# tick-wifi-mk-0_9.net
KiCad netlist of a schematic drawn in EAGLE
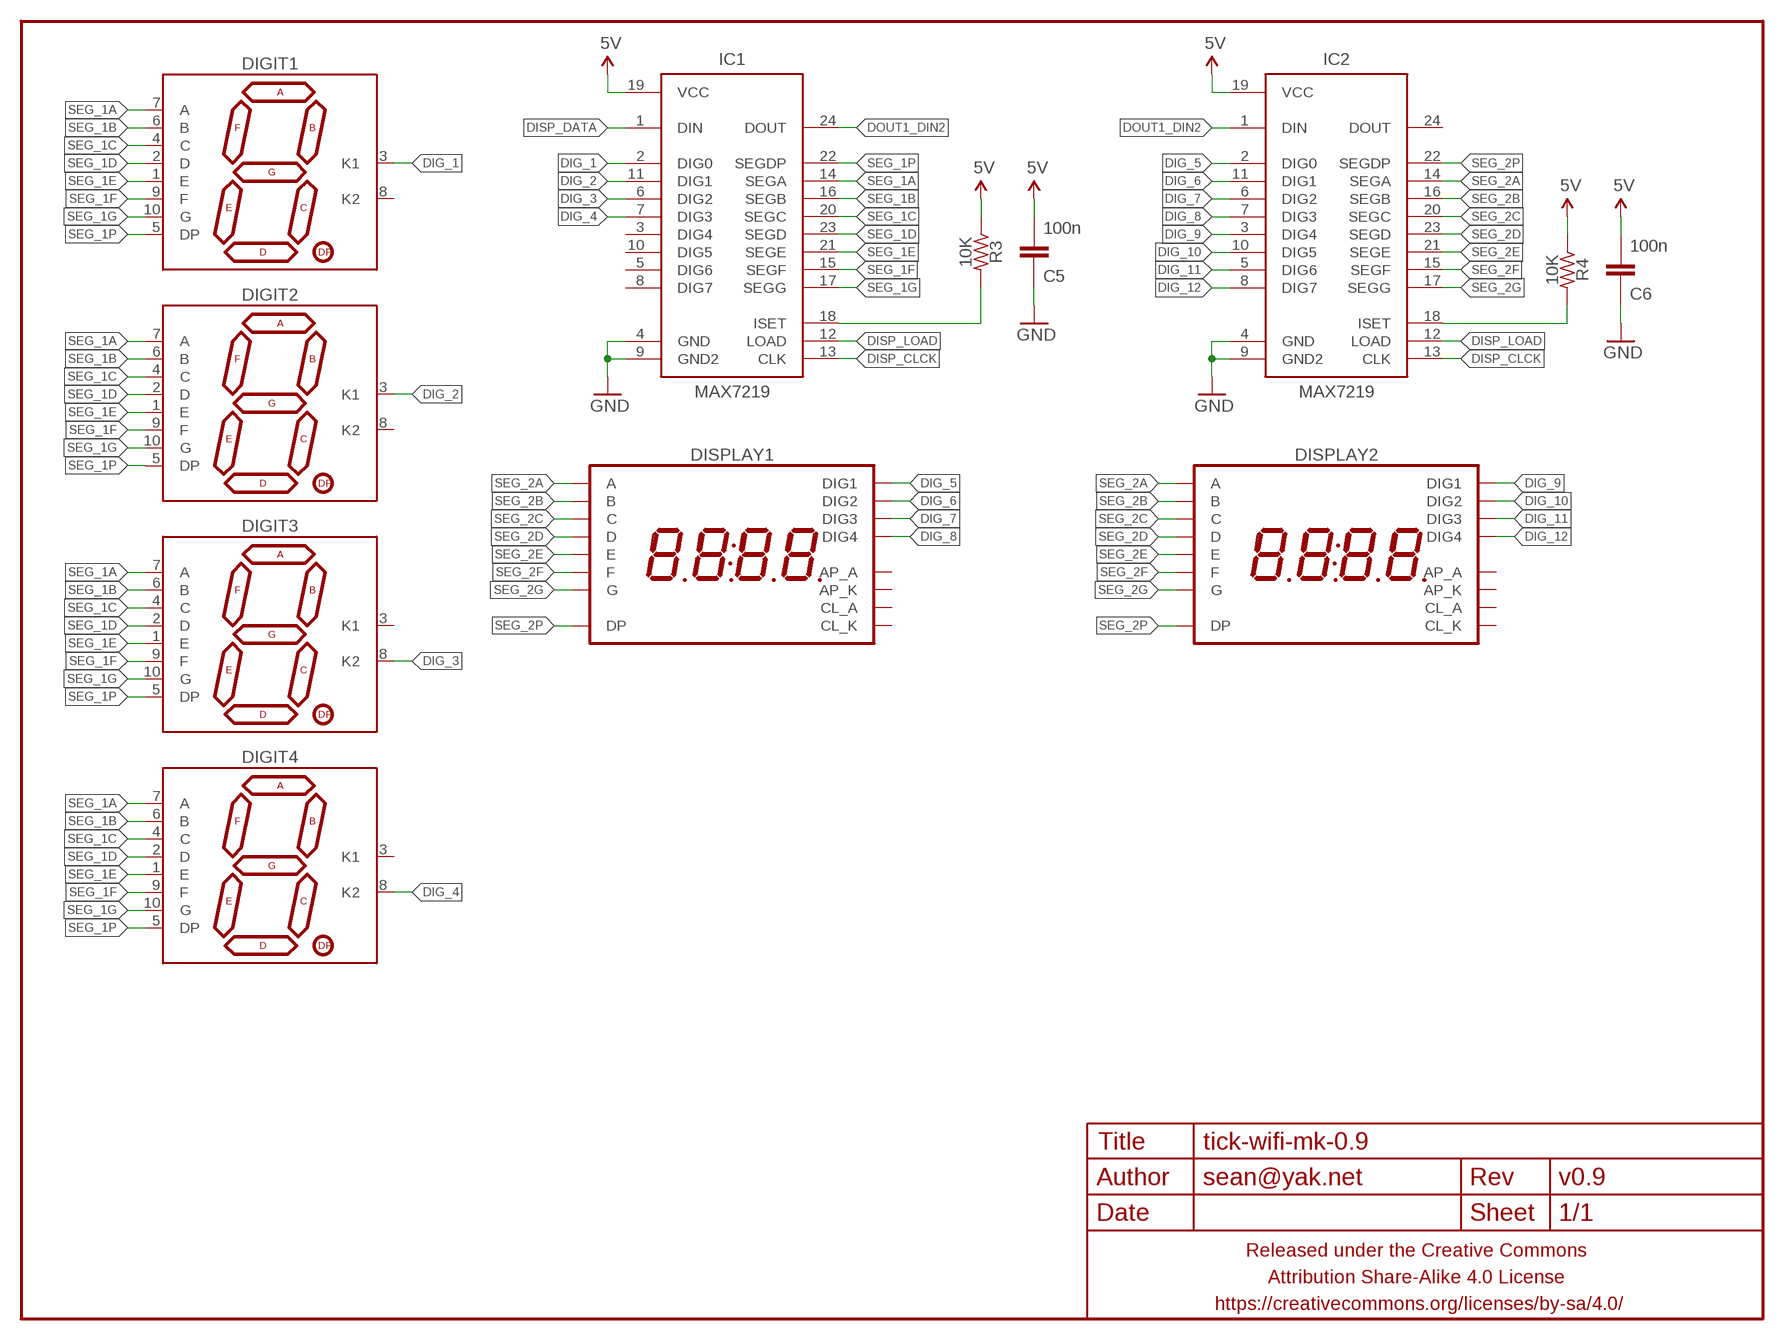
[diagram p0: schematic, sheet 1]

(export (version "E")
  (design (tool "Eeschema 10.0.6"))
  (components
    (comp (ref "C5")
      (value "100n")
      (footprint "eagle-import:C0603")
      (libsource (lib "eagle-import") (part "CAPACITOR-CERAMICC0603"))
    )
    (comp (ref "C6")
      (value "100n")
      (footprint "eagle-import:C0603")
      (libsource (lib "eagle-import") (part "CAPACITOR-CERAMICC0603"))
    )
    (comp (ref "DIGIT1")
      (value "7SEG_1DIGPTH-25.4MM-BARE")
      (footprint "eagle-import:7SEG_1DIG_25.4MM_NOSILK")
      (libsource (lib "eagle-import") (part "7SEG_1DIGPTH-25.4MM-BARE"))
    )
    (comp (ref "DIGIT2")
      (value "7SEG_1DIGPTH-25.4MM-BARE")
      (footprint "eagle-import:7SEG_1DIG_25.4MM_NOSILK")
      (libsource (lib "eagle-import") (part "7SEG_1DIGPTH-25.4MM-BARE"))
    )
    (comp (ref "DIGIT3")
      (value "7SEG_1DIGPTH-25.4MM-BARE")
      (footprint "eagle-import:7SEG_1DIG_25.4MM_NOSILK")
      (libsource (lib "eagle-import") (part "7SEG_1DIGPTH-25.4MM-BARE"))
    )
    (comp (ref "DIGIT4")
      (value "7SEG_1DIGPTH-25.4MM-BARE")
      (footprint "eagle-import:7SEG_1DIG_25.4MM_NOSILK")
      (libsource (lib "eagle-import") (part "7SEG_1DIGPTH-25.4MM-BARE"))
    )
    (comp (ref "DISPLAY1")
      (value "7SEG_4DIGIT_COLON_APOS")
      (footprint "eagle-import:7SEG_4DIG_10MM")
      (libsource (lib "eagle-import") (part "7SEG_4DIGIT_COLON_APOS"))
    )
    (comp (ref "DISPLAY2")
      (value "7SEG_4DIGIT_COLON_APOS")
      (footprint "eagle-import:7SEG_4DIG_10MM")
      (libsource (lib "eagle-import") (part "7SEG_4DIGIT_COLON_APOS"))
    )
    (comp (ref "FRAME1")
      (value "FRAME-LETTERNO_PACKAGE")
      (footprint "eagle-import:DUMMY")
      (fields (field (name "DESIGNER") "sean@yak.net") (field (name "VERSION") "v0.9"))
      (libsource (lib "eagle-import") (part "FRAME-LETTERNO_PACKAGE"))
    )
    (comp (ref "IC1")
      (value "MAX7219")
      (footprint "eagle-import:SO24W")
      (libsource (lib "eagle-import") (part "MAX7219SOIC-W"))
    )
    (comp (ref "IC2")
      (value "MAX7219")
      (footprint "eagle-import:SO24W")
      (libsource (lib "eagle-import") (part "MAX7219SOIC-W"))
    )
    (comp (ref "R3")
      (value "10K")
      (footprint "eagle-import:R0603")
      (libsource (lib "eagle-import") (part "RESISTORR0603"))
    )
    (comp (ref "R4")
      (value "10K")
      (footprint "eagle-import:R0603")
      (libsource (lib "eagle-import") (part "RESISTORR0603"))
    )
  )
  (nets
    (net (code "1") (name "5V") (class "Default")
      (node (ref "C5") (pin "2") (pinfunction "2_2") (pintype "passive"))
      (node (ref "C6") (pin "2") (pinfunction "2_2") (pintype "passive"))
      (node (ref "IC1") (pin "19") (pinfunction "VCC_19") (pintype "bidirectional"))
      (node (ref "IC2") (pin "19") (pinfunction "VCC_19") (pintype "bidirectional"))
      (node (ref "R3") (pin "1") (pinfunction "1_1") (pintype "passive"))
      (node (ref "R4") (pin "1") (pinfunction "1_1") (pintype "passive"))
    )
    (net (code "2") (name "DIG_1") (class "Default")
      (node (ref "DIGIT1") (pin "3") (pinfunction "K1_3") (pintype "bidirectional"))
      (node (ref "IC1") (pin "2") (pinfunction "DIG0_2") (pintype "bidirectional"))
    )
    (net (code "3") (name "DIG_2") (class "Default")
      (node (ref "DIGIT2") (pin "3") (pinfunction "K1_3") (pintype "bidirectional"))
      (node (ref "IC1") (pin "11") (pinfunction "DIG1_11") (pintype "bidirectional"))
    )
    (net (code "4") (name "DIG_3") (class "Default")
      (node (ref "DIGIT3") (pin "8") (pinfunction "K2_8") (pintype "bidirectional"))
      (node (ref "IC1") (pin "6") (pinfunction "DIG2_6") (pintype "bidirectional"))
    )
    (net (code "5") (name "DIG_4") (class "Default")
      (node (ref "DIGIT4") (pin "8") (pinfunction "K2_8") (pintype "bidirectional"))
      (node (ref "IC1") (pin "7") (pinfunction "DIG3_7") (pintype "bidirectional"))
    )
    (net (code "6") (name "DIG_5") (class "Default")
      (node (ref "DISPLAY1") (pin "1") (pinfunction "DIG1_1") (pintype "passive"))
      (node (ref "IC2") (pin "2") (pinfunction "DIG0_2") (pintype "bidirectional"))
    )
    (net (code "7") (name "DIG_6") (class "Default")
      (node (ref "DISPLAY1") (pin "2") (pinfunction "DIG2_2") (pintype "passive"))
      (node (ref "IC2") (pin "11") (pinfunction "DIG1_11") (pintype "bidirectional"))
    )
    (net (code "8") (name "DIG_7") (class "Default")
      (node (ref "DISPLAY1") (pin "6") (pinfunction "DIG3_6") (pintype "passive"))
      (node (ref "IC2") (pin "6") (pinfunction "DIG2_6") (pintype "bidirectional"))
    )
    (net (code "9") (name "DIG_8") (class "Default")
      (node (ref "DISPLAY1") (pin "8") (pinfunction "DIG4_8") (pintype "passive"))
      (node (ref "IC2") (pin "7") (pinfunction "DIG3_7") (pintype "bidirectional"))
    )
    (net (code "10") (name "DIG_9") (class "Default")
      (node (ref "DISPLAY2") (pin "1") (pinfunction "DIG1_1") (pintype "passive"))
      (node (ref "IC2") (pin "3") (pinfunction "DIG4_3") (pintype "bidirectional"))
    )
    (net (code "11") (name "DIG_10") (class "Default")
      (node (ref "DISPLAY2") (pin "2") (pinfunction "DIG2_2") (pintype "passive"))
      (node (ref "IC2") (pin "10") (pinfunction "DIG5_10") (pintype "bidirectional"))
    )
    (net (code "12") (name "DIG_11") (class "Default")
      (node (ref "DISPLAY2") (pin "6") (pinfunction "DIG3_6") (pintype "passive"))
      (node (ref "IC2") (pin "5") (pinfunction "DIG6_5") (pintype "bidirectional"))
    )
    (net (code "13") (name "DIG_12") (class "Default")
      (node (ref "DISPLAY2") (pin "8") (pinfunction "DIG4_8") (pintype "passive"))
      (node (ref "IC2") (pin "8") (pinfunction "DIG7_8") (pintype "bidirectional"))
    )
    (net (code "14") (name "DISP_CLCK") (class "Default")
      (node (ref "IC1") (pin "13") (pinfunction "CLK_13") (pintype "bidirectional"))
      (node (ref "IC2") (pin "13") (pinfunction "CLK_13") (pintype "bidirectional"))
    )
    (net (code "15") (name "DISP_DATA") (class "Default")
      (node (ref "IC1") (pin "1") (pinfunction "DIN_1") (pintype "bidirectional"))
    )
    (net (code "16") (name "DISP_LOAD") (class "Default")
      (node (ref "IC1") (pin "12") (pinfunction "LOAD_12") (pintype "bidirectional"))
      (node (ref "IC2") (pin "12") (pinfunction "LOAD_12") (pintype "bidirectional"))
    )
    (net (code "17") (name "DOUT1_DIN2") (class "Default")
      (node (ref "IC1") (pin "24") (pinfunction "DOUT_24") (pintype "bidirectional"))
      (node (ref "IC2") (pin "1") (pinfunction "DIN_1") (pintype "bidirectional"))
    )
    (net (code "18") (name "GND") (class "Default")
      (node (ref "C5") (pin "1") (pinfunction "1_1") (pintype "passive"))
      (node (ref "C6") (pin "1") (pinfunction "1_1") (pintype "passive"))
      (node (ref "IC1") (pin "4") (pinfunction "GND_4") (pintype "bidirectional"))
      (node (ref "IC1") (pin "9") (pinfunction "GND2_9") (pintype "bidirectional"))
      (node (ref "IC2") (pin "4") (pinfunction "GND_4") (pintype "bidirectional"))
      (node (ref "IC2") (pin "9") (pinfunction "GND2_9") (pintype "bidirectional"))
    )
    (net (code "19") (name "Net-(IC1-ISET)") (class "Default")
      (node (ref "IC1") (pin "18") (pinfunction "ISET_18") (pintype "bidirectional"))
      (node (ref "R3") (pin "2") (pinfunction "2_2") (pintype "passive"))
    )
    (net (code "20") (name "Net-(IC2-ISET)") (class "Default")
      (node (ref "IC2") (pin "18") (pinfunction "ISET_18") (pintype "bidirectional"))
      (node (ref "R4") (pin "2") (pinfunction "2_2") (pintype "passive"))
    )
    (net (code "21") (name "SEG_1A") (class "Default")
      (node (ref "DIGIT1") (pin "7") (pinfunction "A_7") (pintype "bidirectional"))
      (node (ref "DIGIT2") (pin "7") (pinfunction "A_7") (pintype "bidirectional"))
      (node (ref "DIGIT3") (pin "7") (pinfunction "A_7") (pintype "bidirectional"))
      (node (ref "DIGIT4") (pin "7") (pinfunction "A_7") (pintype "bidirectional"))
      (node (ref "IC1") (pin "14") (pinfunction "SEGA_14") (pintype "bidirectional"))
    )
    (net (code "22") (name "SEG_1B") (class "Default")
      (node (ref "DIGIT1") (pin "6") (pinfunction "B_6") (pintype "bidirectional"))
      (node (ref "DIGIT2") (pin "6") (pinfunction "B_6") (pintype "bidirectional"))
      (node (ref "DIGIT3") (pin "6") (pinfunction "B_6") (pintype "bidirectional"))
      (node (ref "DIGIT4") (pin "6") (pinfunction "B_6") (pintype "bidirectional"))
      (node (ref "IC1") (pin "16") (pinfunction "SEGB_16") (pintype "bidirectional"))
    )
    (net (code "23") (name "SEG_1C") (class "Default")
      (node (ref "DIGIT1") (pin "4") (pinfunction "C_4") (pintype "bidirectional"))
      (node (ref "DIGIT2") (pin "4") (pinfunction "C_4") (pintype "bidirectional"))
      (node (ref "DIGIT3") (pin "4") (pinfunction "C_4") (pintype "bidirectional"))
      (node (ref "DIGIT4") (pin "4") (pinfunction "C_4") (pintype "bidirectional"))
      (node (ref "IC1") (pin "20") (pinfunction "SEGC_20") (pintype "bidirectional"))
    )
    (net (code "24") (name "SEG_1D") (class "Default")
      (node (ref "DIGIT1") (pin "2") (pinfunction "D_2") (pintype "bidirectional"))
      (node (ref "DIGIT2") (pin "2") (pinfunction "D_2") (pintype "bidirectional"))
      (node (ref "DIGIT3") (pin "2") (pinfunction "D_2") (pintype "bidirectional"))
      (node (ref "DIGIT4") (pin "2") (pinfunction "D_2") (pintype "bidirectional"))
      (node (ref "IC1") (pin "23") (pinfunction "SEGD_23") (pintype "bidirectional"))
    )
    (net (code "25") (name "SEG_1E") (class "Default")
      (node (ref "DIGIT1") (pin "1") (pinfunction "E_1") (pintype "bidirectional"))
      (node (ref "DIGIT2") (pin "1") (pinfunction "E_1") (pintype "bidirectional"))
      (node (ref "DIGIT3") (pin "1") (pinfunction "E_1") (pintype "bidirectional"))
      (node (ref "DIGIT4") (pin "1") (pinfunction "E_1") (pintype "bidirectional"))
      (node (ref "IC1") (pin "21") (pinfunction "SEGE_21") (pintype "bidirectional"))
    )
    (net (code "26") (name "SEG_1F") (class "Default")
      (node (ref "DIGIT1") (pin "9") (pinfunction "F_9") (pintype "bidirectional"))
      (node (ref "DIGIT2") (pin "9") (pinfunction "F_9") (pintype "bidirectional"))
      (node (ref "DIGIT3") (pin "9") (pinfunction "F_9") (pintype "bidirectional"))
      (node (ref "DIGIT4") (pin "9") (pinfunction "F_9") (pintype "bidirectional"))
      (node (ref "IC1") (pin "15") (pinfunction "SEGF_15") (pintype "bidirectional"))
    )
    (net (code "27") (name "SEG_1G") (class "Default")
      (node (ref "DIGIT1") (pin "10") (pinfunction "G_10") (pintype "bidirectional"))
      (node (ref "DIGIT2") (pin "10") (pinfunction "G_10") (pintype "bidirectional"))
      (node (ref "DIGIT3") (pin "10") (pinfunction "G_10") (pintype "bidirectional"))
      (node (ref "DIGIT4") (pin "10") (pinfunction "G_10") (pintype "bidirectional"))
      (node (ref "IC1") (pin "17") (pinfunction "SEGG_17") (pintype "bidirectional"))
    )
    (net (code "28") (name "SEG_1P") (class "Default")
      (node (ref "DIGIT1") (pin "5") (pinfunction "DP_5") (pintype "bidirectional"))
      (node (ref "DIGIT2") (pin "5") (pinfunction "DP_5") (pintype "bidirectional"))
      (node (ref "DIGIT3") (pin "5") (pinfunction "DP_5") (pintype "bidirectional"))
      (node (ref "DIGIT4") (pin "5") (pinfunction "DP_5") (pintype "bidirectional"))
      (node (ref "IC1") (pin "22") (pinfunction "SEGDP_22") (pintype "bidirectional"))
    )
    (net (code "29") (name "SEG_2A") (class "Default")
      (node (ref "DISPLAY1") (pin "14") (pinfunction "A_14") (pintype "passive"))
      (node (ref "DISPLAY2") (pin "14") (pinfunction "A_14") (pintype "passive"))
      (node (ref "IC2") (pin "14") (pinfunction "SEGA_14") (pintype "bidirectional"))
    )
    (net (code "30") (name "SEG_2B") (class "Default")
      (node (ref "DISPLAY1") (pin "16") (pinfunction "B_16") (pintype "passive"))
      (node (ref "DISPLAY2") (pin "16") (pinfunction "B_16") (pintype "passive"))
      (node (ref "IC2") (pin "16") (pinfunction "SEGB_16") (pintype "bidirectional"))
    )
    (net (code "31") (name "SEG_2C") (class "Default")
      (node (ref "DISPLAY1") (pin "13") (pinfunction "C_13") (pintype "passive"))
      (node (ref "DISPLAY2") (pin "13") (pinfunction "C_13") (pintype "passive"))
      (node (ref "IC2") (pin "20") (pinfunction "SEGC_20") (pintype "bidirectional"))
    )
    (net (code "32") (name "SEG_2D") (class "Default")
      (node (ref "DISPLAY1") (pin "3") (pinfunction "D_3") (pintype "passive"))
      (node (ref "DISPLAY2") (pin "3") (pinfunction "D_3") (pintype "passive"))
      (node (ref "IC2") (pin "23") (pinfunction "SEGD_23") (pintype "bidirectional"))
    )
    (net (code "33") (name "SEG_2E") (class "Default")
      (node (ref "DISPLAY1") (pin "5") (pinfunction "E_5") (pintype "passive"))
      (node (ref "DISPLAY2") (pin "5") (pinfunction "E_5") (pintype "passive"))
      (node (ref "IC2") (pin "21") (pinfunction "SEGE_21") (pintype "bidirectional"))
    )
    (net (code "34") (name "SEG_2F") (class "Default")
      (node (ref "DISPLAY1") (pin "11") (pinfunction "F_11") (pintype "passive"))
      (node (ref "DISPLAY2") (pin "11") (pinfunction "F_11") (pintype "passive"))
      (node (ref "IC2") (pin "15") (pinfunction "SEGF_15") (pintype "bidirectional"))
    )
    (net (code "35") (name "SEG_2G") (class "Default")
      (node (ref "DISPLAY1") (pin "15") (pinfunction "G_15") (pintype "passive"))
      (node (ref "DISPLAY2") (pin "15") (pinfunction "G_15") (pintype "passive"))
      (node (ref "IC2") (pin "17") (pinfunction "SEGG_17") (pintype "bidirectional"))
    )
    (net (code "36") (name "SEG_2P") (class "Default")
      (node (ref "DISPLAY1") (pin "7") (pinfunction "DP_7") (pintype "passive"))
      (node (ref "DISPLAY2") (pin "7") (pinfunction "DP_7") (pintype "passive"))
      (node (ref "IC2") (pin "22") (pinfunction "SEGDP_22") (pintype "bidirectional"))
    )
    (net (code "37") (name "unconnected-(DIGIT1-K2-Pad8)") (class "Default")
      (node (ref "DIGIT1") (pin "8") (pinfunction "K2_8") (pintype "bidirectional"))
    )
    (net (code "38") (name "unconnected-(DIGIT2-K2-Pad8)") (class "Default")
      (node (ref "DIGIT2") (pin "8") (pinfunction "K2_8") (pintype "bidirectional"))
    )
    (net (code "39") (name "unconnected-(DIGIT3-K1-Pad3)") (class "Default")
      (node (ref "DIGIT3") (pin "3") (pinfunction "K1_3") (pintype "bidirectional"))
    )
    (net (code "40") (name "unconnected-(DIGIT4-K1-Pad3)") (class "Default")
      (node (ref "DIGIT4") (pin "3") (pinfunction "K1_3") (pintype "bidirectional"))
    )
    (net (code "41") (name "unconnected-(DISPLAY1-AP_A-Pad10)") (class "Default")
      (node (ref "DISPLAY1") (pin "10") (pinfunction "AP_A_10") (pintype "bidirectional"))
    )
    (net (code "42") (name "unconnected-(DISPLAY1-AP_K-Pad9)") (class "Default")
      (node (ref "DISPLAY1") (pin "9") (pinfunction "AP_K_9") (pintype "bidirectional"))
    )
    (net (code "43") (name "unconnected-(DISPLAY1-CL_A-Pad4)") (class "Default")
      (node (ref "DISPLAY1") (pin "4") (pinfunction "CL_A_4") (pintype "passive"))
    )
    (net (code "44") (name "unconnected-(DISPLAY1-CL_K-Pad12)") (class "Default")
      (node (ref "DISPLAY1") (pin "12") (pinfunction "CL_K_12") (pintype "passive"))
    )
    (net (code "45") (name "unconnected-(DISPLAY2-AP_A-Pad10)") (class "Default")
      (node (ref "DISPLAY2") (pin "10") (pinfunction "AP_A_10") (pintype "bidirectional"))
    )
    (net (code "46") (name "unconnected-(DISPLAY2-AP_K-Pad9)") (class "Default")
      (node (ref "DISPLAY2") (pin "9") (pinfunction "AP_K_9") (pintype "bidirectional"))
    )
    (net (code "47") (name "unconnected-(DISPLAY2-CL_A-Pad4)") (class "Default")
      (node (ref "DISPLAY2") (pin "4") (pinfunction "CL_A_4") (pintype "passive"))
    )
    (net (code "48") (name "unconnected-(DISPLAY2-CL_K-Pad12)") (class "Default")
      (node (ref "DISPLAY2") (pin "12") (pinfunction "CL_K_12") (pintype "passive"))
    )
    (net (code "49") (name "unconnected-(IC1-DIG4-Pad3)") (class "Default")
      (node (ref "IC1") (pin "3") (pinfunction "DIG4_3") (pintype "bidirectional"))
    )
    (net (code "50") (name "unconnected-(IC1-DIG5-Pad10)") (class "Default")
      (node (ref "IC1") (pin "10") (pinfunction "DIG5_10") (pintype "bidirectional"))
    )
    (net (code "51") (name "unconnected-(IC1-DIG6-Pad5)") (class "Default")
      (node (ref "IC1") (pin "5") (pinfunction "DIG6_5") (pintype "bidirectional"))
    )
    (net (code "52") (name "unconnected-(IC1-DIG7-Pad8)") (class "Default")
      (node (ref "IC1") (pin "8") (pinfunction "DIG7_8") (pintype "bidirectional"))
    )
    (net (code "53") (name "unconnected-(IC2-DOUT-Pad24)") (class "Default")
      (node (ref "IC2") (pin "24") (pinfunction "DOUT_24") (pintype "bidirectional"))
    )
  )
)
